# xkid_0_3.net
KiCad netlist of a schematic drawn in EAGLE
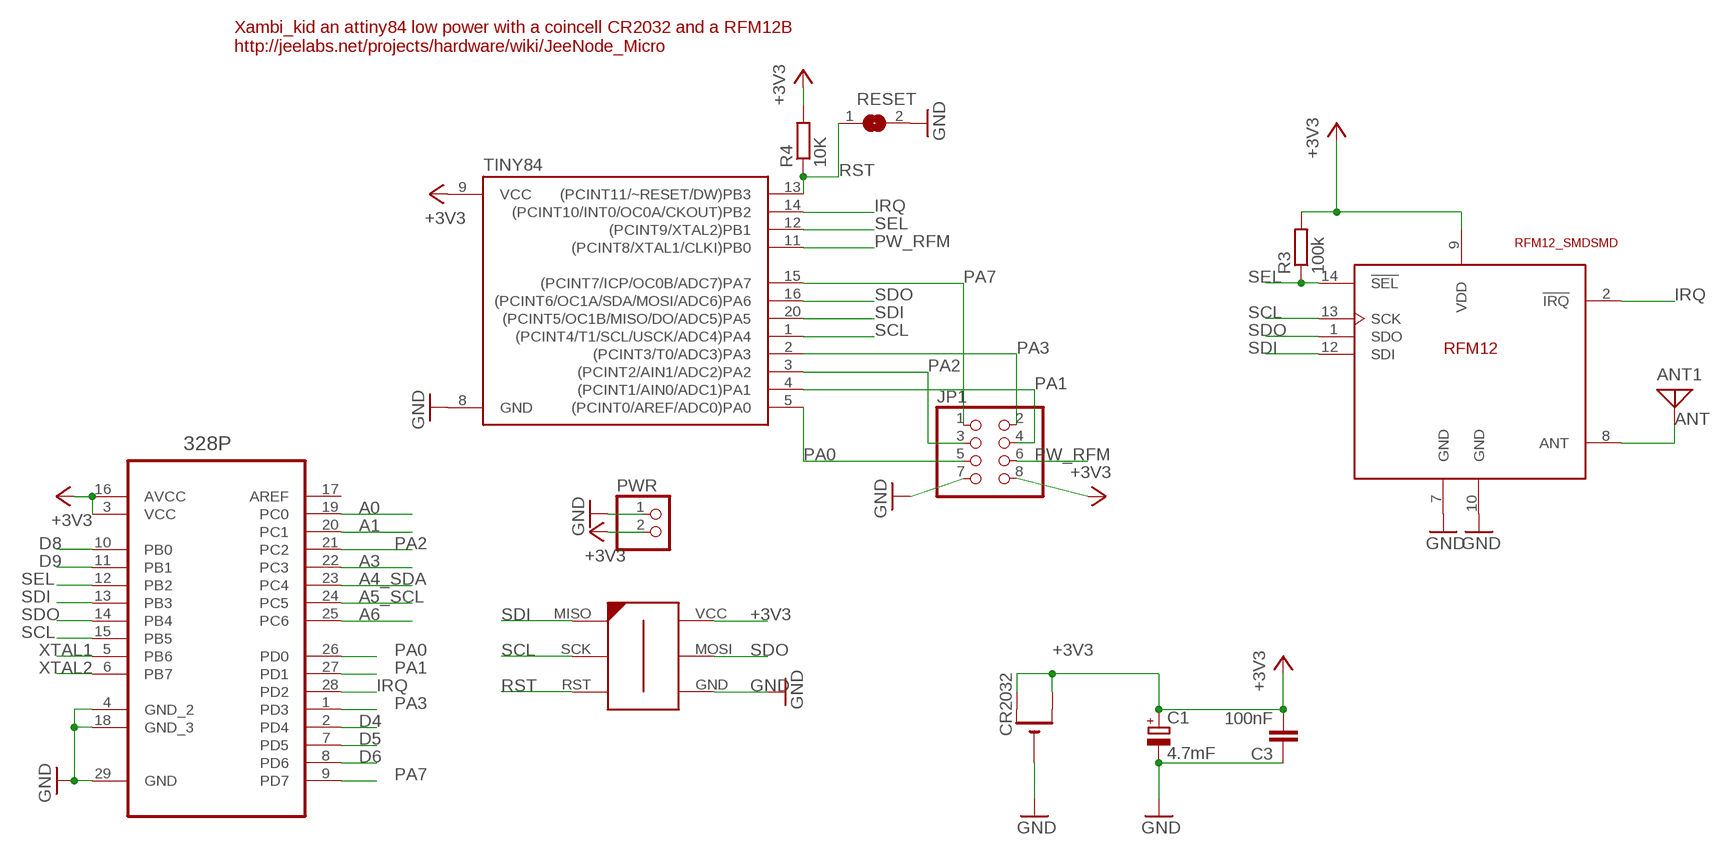
[diagram p0: schematic, sheet 1]

(export (version "E")
  (design (tool "Eeschema 10.0.6"))
  (components
    (comp (ref "328P")
      (value "ATMEGA328P-MMH")
      (footprint "eagle-import:QFN45P400X400X100-29N")
      (libsource (lib "eagle-import") (part "ATMEGA328P-MMH"))
    )
    (comp (ref "ANT1")
      (value "ANTENNA")
      (footprint "eagle-import:PAD-01")
      (libsource (lib "eagle-import") (part "ANTENNA"))
    )
    (comp (ref "C1")
      (value "4.7mF")
      (footprint "eagle-import:CT3216")
      (libsource (lib "eagle-import") (part "CPOL-EUCT3216"))
    )
    (comp (ref "C3")
      (value "100nF")
      (footprint "eagle-import:C0805K")
      (libsource (lib "eagle-import") (part "C-EUC0805K"))
    )
    (comp (ref "CR2032")
      (value "CR2032SMT")
      (footprint "eagle-import:CR2032-SMD")
      (libsource (lib "eagle-import") (part "CR2032SMT"))
    )
    (comp (ref "JP1")
      (value "PINHD-2X4_2.54")
      (footprint "eagle-import:2X04")
      (libsource (lib "eagle-import") (part "PINHD-2X4_2.54"))
    )
    (comp (ref "PWR")
      (value "PINHD-1X2")
      (footprint "eagle-import:1X02")
      (libsource (lib "eagle-import") (part "PINHD-1X2"))
    )
    (comp (ref "R3")
      (value "100k")
      (footprint "eagle-import:R0805")
      (libsource (lib "eagle-import") (part "R-EU_R0805"))
    )
    (comp (ref "R4")
      (value "10K")
      (footprint "eagle-import:R0805")
      (libsource (lib "eagle-import") (part "R-EU_R0805"))
    )
    (comp (ref "RESET")
      (value "SJ")
      (footprint "eagle-import:SJ")
      (libsource (lib "eagle-import") (part "SJ"))
    )
    (comp (ref "TINY84")
      (value "ATTINY84ATTINY84-20MU")
      (footprint "eagle-import:QFN20")
      (libsource (lib "eagle-import") (part "ATTINY84ATTINY84-20MU"))
    )
    (comp (ref "U$1")
      (value "RFM12_SMDSMD")
      (footprint "eagle-import:RFM12")
      (libsource (lib "eagle-import") (part "RFM12_SMDSMD"))
    )
    (comp (ref "U$2")
      (value "AVR-ISP-6-EDGE")
      (footprint "eagle-import:6PAD_ISP")
      (libsource (lib "eagle-import") (part "AVR-ISP-6-EDGE"))
    )
  )
  (nets
    (net (code "1") (name "+3V3") (class "Default")
      (node (ref "328P") (pin "16") (pinfunction "AVCC_16") (pintype "power_in"))
      (node (ref "328P") (pin "3") (pinfunction "VCC_3") (pintype "power_in"))
      (node (ref "C1") (pin "+") (pinfunction "+_+") (pintype "passive"))
      (node (ref "C3") (pin "2") (pinfunction "2_2") (pintype "passive"))
      (node (ref "CR2032") (pin "+$1") (pinfunction "+_+$1") (pintype "passive"))
      (node (ref "CR2032") (pin "+$2") (pinfunction "+1_+$2") (pintype "passive"))
      (node (ref "JP1") (pin "8") (pinfunction "8_8") (pintype "passive"))
      (node (ref "PWR") (pin "2") (pinfunction "2_2") (pintype "passive"))
      (node (ref "R3") (pin "2") (pinfunction "2_2") (pintype "passive"))
      (node (ref "R4") (pin "2") (pinfunction "2_2") (pintype "passive"))
      (node (ref "TINY84") (pin "9") (pinfunction "VCC_9") (pintype "bidirectional"))
      (node (ref "U$1") (pin "9") (pinfunction "VDD_9") (pintype "power_in"))
      (node (ref "U$2") (pin "VCC") (pinfunction "P$6_VCC") (pintype "bidirectional"))
    )
    (net (code "2") (name "/A0") (class "Default")
      (node (ref "328P") (pin "19") (pinfunction "PC0_19") (pintype "bidirectional"))
    )
    (net (code "3") (name "/A1") (class "Default")
      (node (ref "328P") (pin "20") (pinfunction "PC1_20") (pintype "bidirectional"))
    )
    (net (code "4") (name "/A3") (class "Default")
      (node (ref "328P") (pin "22") (pinfunction "PC3_22") (pintype "bidirectional"))
    )
    (net (code "5") (name "/A4_SDA") (class "Default")
      (node (ref "328P") (pin "23") (pinfunction "PC4_23") (pintype "bidirectional"))
    )
    (net (code "6") (name "/A5_SCL") (class "Default")
      (node (ref "328P") (pin "24") (pinfunction "PC5_24") (pintype "bidirectional"))
    )
    (net (code "7") (name "/A6") (class "Default")
      (node (ref "328P") (pin "25") (pinfunction "PC6_25") (pintype "bidirectional"))
    )
    (net (code "8") (name "/ANT") (class "Default")
      (node (ref "ANT1") (pin "1") (pinfunction "1_1") (pintype "output"))
      (node (ref "U$1") (pin "8") (pinfunction "ANT_8") (pintype "bidirectional"))
    )
    (net (code "9") (name "/D4") (class "Default")
      (node (ref "328P") (pin "2") (pinfunction "PD4_2") (pintype "bidirectional"))
    )
    (net (code "10") (name "/D5") (class "Default")
      (node (ref "328P") (pin "7") (pinfunction "PD5_7") (pintype "bidirectional"))
    )
    (net (code "11") (name "/D6") (class "Default")
      (node (ref "328P") (pin "8") (pinfunction "PD6_8") (pintype "bidirectional"))
    )
    (net (code "12") (name "/D8") (class "Default")
      (node (ref "328P") (pin "10") (pinfunction "PB0_10") (pintype "bidirectional"))
    )
    (net (code "13") (name "/D9") (class "Default")
      (node (ref "328P") (pin "11") (pinfunction "PB1_11") (pintype "bidirectional"))
    )
    (net (code "14") (name "/IRQ") (class "Default")
      (node (ref "328P") (pin "28") (pinfunction "PD2_28") (pintype "bidirectional"))
      (node (ref "TINY84") (pin "14") (pinfunction "(PCINT10/INT0/OC0A/CKOUT)PB2_14") (pintype "bidirectional"))
      (node (ref "U$1") (pin "2") (pinfunction "~{IRQ}_2") (pintype "output"))
    )
    (net (code "15") (name "/PA0") (class "Default")
      (node (ref "328P") (pin "26") (pinfunction "PD0_26") (pintype "bidirectional"))
      (node (ref "JP1") (pin "5") (pinfunction "5_5") (pintype "passive"))
      (node (ref "TINY84") (pin "5") (pinfunction "(PCINT0/AREF/ADC0)PA0_5") (pintype "bidirectional"))
    )
    (net (code "16") (name "/PA1") (class "Default")
      (node (ref "328P") (pin "27") (pinfunction "PD1_27") (pintype "bidirectional"))
      (node (ref "JP1") (pin "4") (pinfunction "4_4") (pintype "passive"))
      (node (ref "TINY84") (pin "4") (pinfunction "(PCINT1/AIN0/ADC1)PA1_4") (pintype "bidirectional"))
    )
    (net (code "17") (name "/PA2") (class "Default")
      (node (ref "328P") (pin "21") (pinfunction "PC2_21") (pintype "bidirectional"))
      (node (ref "JP1") (pin "3") (pinfunction "3_3") (pintype "passive"))
      (node (ref "TINY84") (pin "3") (pinfunction "(PCINT2/AIN1/ADC2)PA2_3") (pintype "bidirectional"))
    )
    (net (code "18") (name "/PA3") (class "Default")
      (node (ref "328P") (pin "1") (pinfunction "PD3_1") (pintype "bidirectional"))
      (node (ref "JP1") (pin "2") (pinfunction "2_2") (pintype "passive"))
      (node (ref "TINY84") (pin "2") (pinfunction "(PCINT3/T0/ADC3)PA3_2") (pintype "bidirectional"))
    )
    (net (code "19") (name "/PA7") (class "Default")
      (node (ref "328P") (pin "9") (pinfunction "PD7_9") (pintype "bidirectional"))
      (node (ref "JP1") (pin "1") (pinfunction "1_1") (pintype "passive"))
      (node (ref "TINY84") (pin "15") (pinfunction "(PCINT7/ICP/OC0B/ADC7)PA7_15") (pintype "bidirectional"))
    )
    (net (code "20") (name "/PW_RFM") (class "Default")
      (node (ref "JP1") (pin "6") (pinfunction "6_6") (pintype "passive"))
      (node (ref "TINY84") (pin "11") (pinfunction "(PCINT8/XTAL1/CLKI)PB0_11") (pintype "bidirectional"))
    )
    (net (code "21") (name "/RST") (class "Default")
      (node (ref "R4") (pin "1") (pinfunction "1_1") (pintype "passive"))
      (node (ref "RESET") (pin "1") (pinfunction "1_1") (pintype "passive"))
      (node (ref "TINY84") (pin "13") (pinfunction "(PCINT11/~{RESET/DW})PB3_13") (pintype "bidirectional"))
      (node (ref "U$2") (pin "RST") (pinfunction "P$3_RST") (pintype "bidirectional"))
    )
    (net (code "22") (name "/SCL") (class "Default")
      (node (ref "328P") (pin "15") (pinfunction "PB5_15") (pintype "bidirectional"))
      (node (ref "TINY84") (pin "1") (pinfunction "(PCINT4/T1/SCL/USCK/ADC4)PA4_1") (pintype "bidirectional"))
      (node (ref "U$1") (pin "13") (pinfunction "SCK_13") (pintype "input"))
      (node (ref "U$2") (pin "SCK") (pinfunction "P$2_SCK") (pintype "bidirectional"))
    )
    (net (code "23") (name "/SDI") (class "Default")
      (node (ref "328P") (pin "13") (pinfunction "PB3_13") (pintype "bidirectional"))
      (node (ref "TINY84") (pin "20") (pinfunction "(PCINT5/OC1B/MISO/DO/ADC5)PA5_20") (pintype "bidirectional"))
      (node (ref "U$1") (pin "12") (pinfunction "SDI_12") (pintype "input"))
      (node (ref "U$2") (pin "MISO") (pinfunction "P$1_MISO") (pintype "bidirectional"))
    )
    (net (code "24") (name "/SDO") (class "Default")
      (node (ref "328P") (pin "14") (pinfunction "PB4_14") (pintype "bidirectional"))
      (node (ref "TINY84") (pin "16") (pinfunction "(PCINT6/OC1A/SDA/MOSI/ADC6)PA6_16") (pintype "bidirectional"))
      (node (ref "U$1") (pin "1") (pinfunction "SDO_1") (pintype "output"))
      (node (ref "U$2") (pin "MOSI") (pinfunction "P$5_MOSI") (pintype "bidirectional"))
    )
    (net (code "25") (name "/SEL") (class "Default")
      (node (ref "328P") (pin "12") (pinfunction "PB2_12") (pintype "bidirectional"))
      (node (ref "R3") (pin "1") (pinfunction "1_1") (pintype "passive"))
      (node (ref "TINY84") (pin "12") (pinfunction "(PCINT9/XTAL2)PB1_12") (pintype "bidirectional"))
      (node (ref "U$1") (pin "14") (pinfunction "~{SEL}_14") (pintype "input"))
    )
    (net (code "26") (name "/XTAL1") (class "Default")
      (node (ref "328P") (pin "5") (pinfunction "PB6_5") (pintype "bidirectional"))
    )
    (net (code "27") (name "/XTAL2") (class "Default")
      (node (ref "328P") (pin "6") (pinfunction "PB7_6") (pintype "bidirectional"))
    )
    (net (code "28") (name "GND") (class "Default")
      (node (ref "328P") (pin "18") (pinfunction "GND_3_18") (pintype "power_in"))
      (node (ref "328P") (pin "29") (pinfunction "GND_29") (pintype "power_in"))
      (node (ref "328P") (pin "4") (pinfunction "GND_2_4") (pintype "power_in"))
      (node (ref "C1") (pin "-") (pinfunction "-_-") (pintype "passive"))
      (node (ref "C3") (pin "1") (pinfunction "1_1") (pintype "passive"))
      (node (ref "CR2032") (pin "-") (pinfunction "-_-") (pintype "passive"))
      (node (ref "JP1") (pin "7") (pinfunction "7_7") (pintype "passive"))
      (node (ref "PWR") (pin "1") (pinfunction "1_1") (pintype "passive"))
      (node (ref "RESET") (pin "2") (pinfunction "2_2") (pintype "passive"))
      (node (ref "TINY84") (pin "8") (pinfunction "GND_8") (pintype "bidirectional"))
      (node (ref "U$1") (pin "10") (pinfunction "GND_10") (pintype "passive"))
      (node (ref "U$1") (pin "7") (pinfunction "GND_7") (pintype "passive"))
      (node (ref "U$2") (pin "GND") (pinfunction "P$4_GND") (pintype "bidirectional"))
    )
    (net (code "29") (name "unconnected-(328P-AREF-Pad17)") (class "Default")
      (node (ref "328P") (pin "17") (pinfunction "AREF_17") (pintype "passive"))
    )
  )
)
